# Hydrophones.net
KiCad netlist of a schematic drawn in Altium Designer
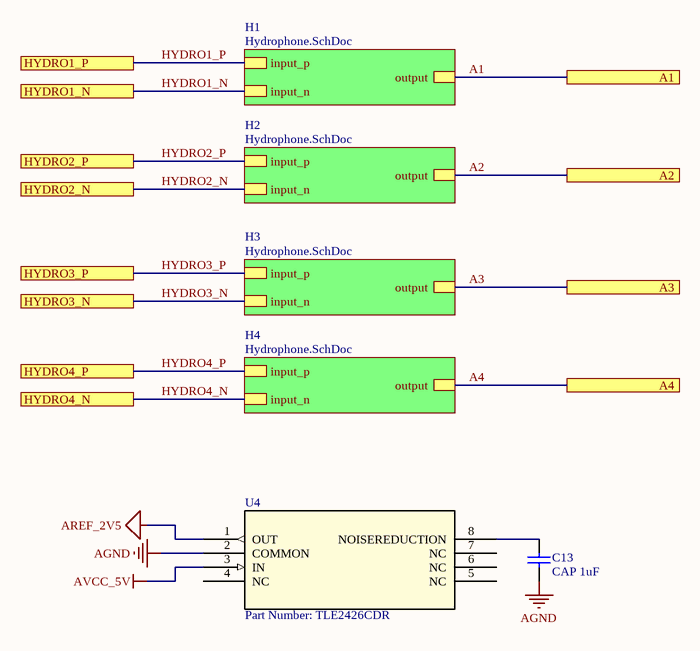
[diagram p0: Hydrophones.SchDoc]

(export (version "E")
  (design (tool "Eeschema 10.0.6"))
  (components
    (comp (ref "C13")
      (value "CAP 1uF")
      (footprint "CAPC0603(1608)100_N")
      (description "CAP 1uF 16V ±5% 0603 (1608 Metric) Thickness 1mm SMD")
      (fields (field (name "TOLERANCE") "Â±5%"))
      (libsource (lib "Altium Content Vault") (part "CAP"))
    )
    (comp (ref "U4")
      (value "Part Number: TLE2426CDR")
      (footprint "D8")
      (description "No Description Available")
      (fields
        (field (name "MANUFACTURER_PART_NUMBER") "TLE2426CDR")
        (field (name "COPYRIGHT") "Copyright (C) 2018 Accelerated Designs. All rights reserved")
      )
      (libsource (lib "Tauv-Lib") (part "TLE2426CDR"))
    )
  )
  (nets
    (net (code "13") (name "AGND") (class "Default")
      (node (ref "C13") (pin "1") (pinfunction "1_1") (pintype "passive"))
      (node (ref "U4") (pin "2") (pinfunction "COMMON_2") (pintype "passive"))
    )
    (net (code "14") (name "AREF_2V5") (class "Default")
      (node (ref "U4") (pin "1") (pinfunction "OUT_1") (pintype "output"))
    )
    (net (code "15") (name "AVCC_5V") (class "Default")
      (node (ref "U4") (pin "3") (pinfunction "IN_3") (pintype "input"))
    )
    (net (code "16") (name "Net-(U4-NOISEREDUCTION)") (class "Default")
      (node (ref "C13") (pin "2") (pinfunction "2_2") (pintype "passive"))
      (node (ref "U4") (pin "8") (pinfunction "NOISEREDUCTION_8") (pintype "passive"))
    )
    (net (code "17") (name "unconnected-(U4-NC-Pad4)") (class "Default")
      (node (ref "U4") (pin "4") (pinfunction "NC_4") (pintype "passive"))
    )
    (net (code "18") (name "unconnected-(U4-NC-Pad5)") (class "Default")
      (node (ref "U4") (pin "5") (pinfunction "NC_5") (pintype "passive"))
    )
    (net (code "19") (name "unconnected-(U4-NC-Pad6)") (class "Default")
      (node (ref "U4") (pin "6") (pinfunction "NC_6") (pintype "passive"))
    )
    (net (code "20") (name "unconnected-(U4-NC-Pad7)") (class "Default")
      (node (ref "U4") (pin "7") (pinfunction "NC_7") (pintype "passive"))
    )
  )
)
